# custom_line_V1_mux1.net
KiCad netlist of a schematic drawn in Altium Designer
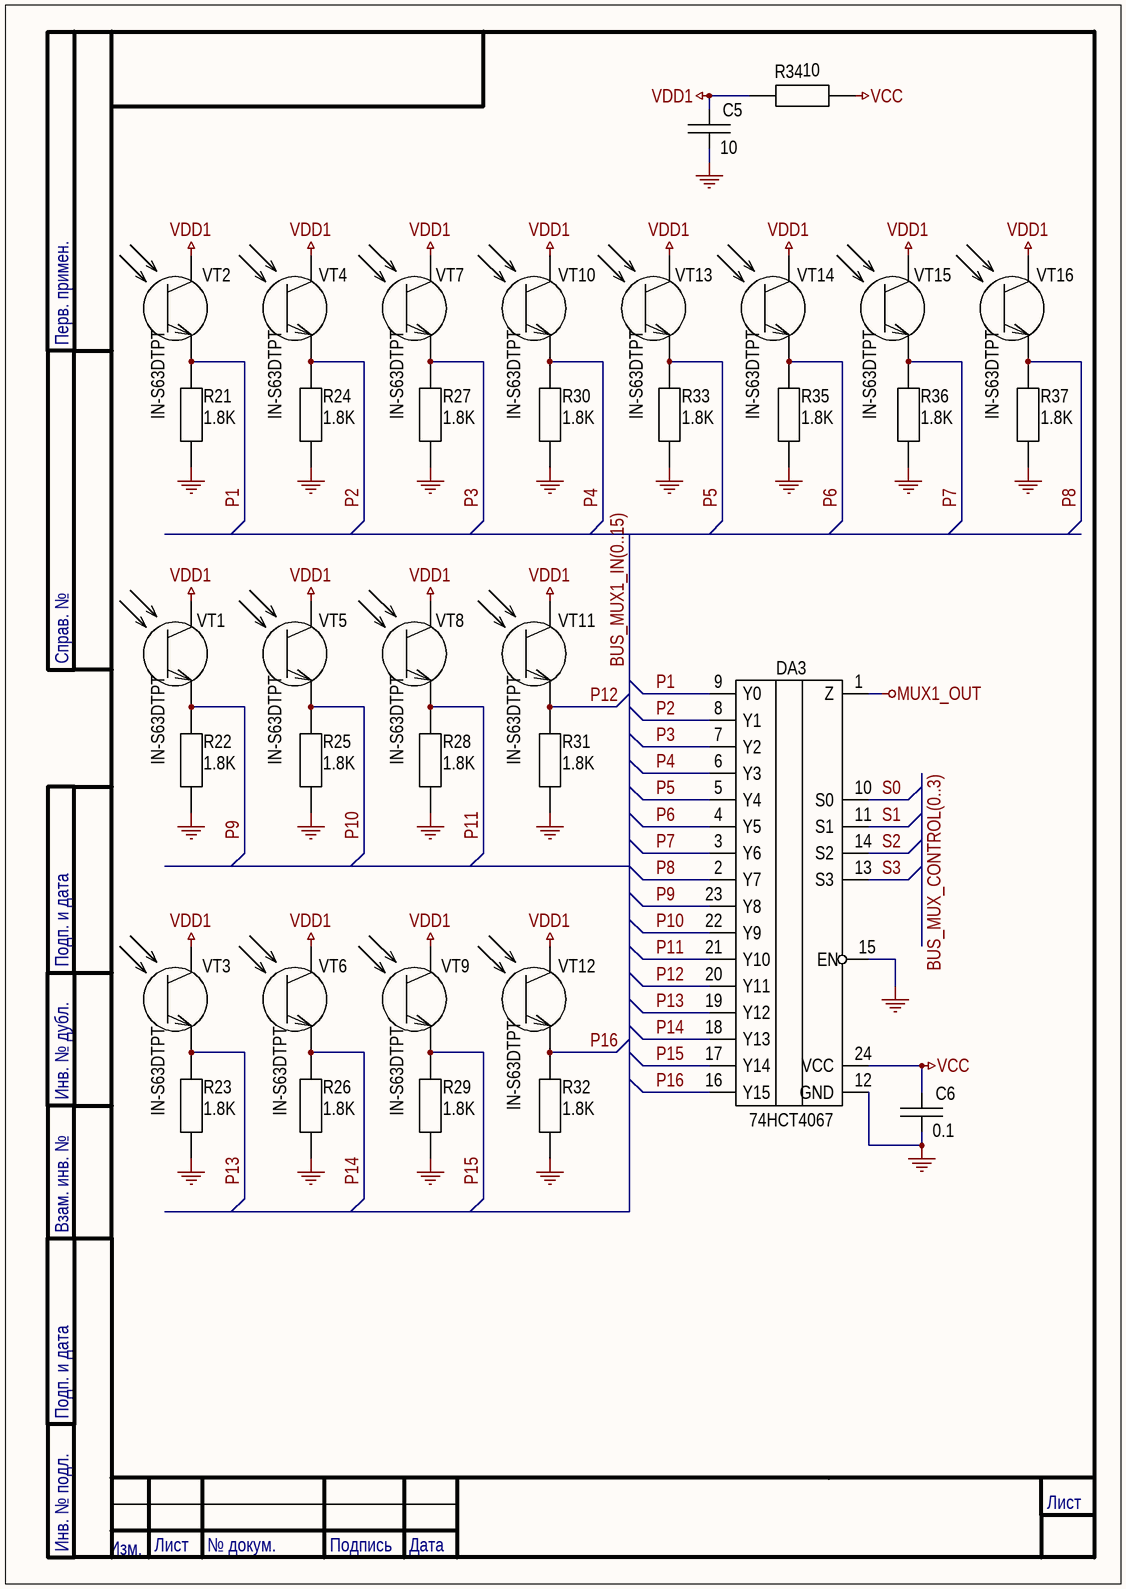
[diagram p0: custom_line_V1_mux1.SchDoc]

(export (version "E")
  (design (tool "Eeschema 10.0.6"))
  (components
    (comp (ref "C5") (value "10") (footprint "CC_0805") (libsource (lib "my_discrete_new") (part "C")))
    (comp (ref "C6") (value "0.1") (footprint "CC_0603") (libsource (lib "my_discrete_new") (part "C")))
    (comp (ref "DA3")
      (value "74HC4067")
      (footprint "TSSOP-24")
      (description "74HC4067PW")
      (fields (field (name "TYPE") "74HCT4067"))
      (libsource (lib "my_microschems_new") (part "74HCT4067"))
    )
    (comp (ref "R21")
      (value "1.8K")
      (footprint "RC_0603_SMALL")
      (fields (field (name "POWER") "0.125W"))
      (libsource (lib "my_discrete_new") (part "R"))
    )
    (comp (ref "R22")
      (value "1.8K")
      (footprint "RC_0603_SMALL")
      (fields (field (name "POWER") "0.125W"))
      (libsource (lib "my_discrete_new") (part "R"))
    )
    (comp (ref "R23")
      (value "1.8K")
      (footprint "RC_0603_SMALL")
      (fields (field (name "POWER") "0.125W"))
      (libsource (lib "my_discrete_new") (part "R"))
    )
    (comp (ref "R24")
      (value "1.8K")
      (footprint "RC_0603_SMALL")
      (fields (field (name "POWER") "0.125W"))
      (libsource (lib "my_discrete_new") (part "R"))
    )
    (comp (ref "R25")
      (value "1.8K")
      (footprint "RC_0603_SMALL")
      (fields (field (name "POWER") "0.125W"))
      (libsource (lib "my_discrete_new") (part "R"))
    )
    (comp (ref "R26")
      (value "1.8K")
      (footprint "RC_0603_SMALL")
      (fields (field (name "POWER") "0.125W"))
      (libsource (lib "my_discrete_new") (part "R"))
    )
    (comp (ref "R27")
      (value "1.8K")
      (footprint "RC_0603_SMALL")
      (fields (field (name "POWER") "0.125W"))
      (libsource (lib "my_discrete_new") (part "R"))
    )
    (comp (ref "R28")
      (value "1.8K")
      (footprint "RC_0603_SMALL")
      (fields (field (name "POWER") "0.125W"))
      (libsource (lib "my_discrete_new") (part "R"))
    )
    (comp (ref "R29")
      (value "1.8K")
      (footprint "RC_0603_SMALL")
      (fields (field (name "POWER") "0.125W"))
      (libsource (lib "my_discrete_new") (part "R"))
    )
    (comp (ref "R30")
      (value "1.8K")
      (footprint "RC_0603_SMALL")
      (fields (field (name "POWER") "0.125W"))
      (libsource (lib "my_discrete_new") (part "R"))
    )
    (comp (ref "R31")
      (value "1.8K")
      (footprint "RC_0603_SMALL")
      (fields (field (name "POWER") "0.125W"))
      (libsource (lib "my_discrete_new") (part "R"))
    )
    (comp (ref "R32")
      (value "1.8K")
      (footprint "RC_0603_SMALL")
      (fields (field (name "POWER") "0.125W"))
      (libsource (lib "my_discrete_new") (part "R"))
    )
    (comp (ref "R33")
      (value "1.8K")
      (footprint "RC_0603_SMALL")
      (fields (field (name "POWER") "0.125W"))
      (libsource (lib "my_discrete_new") (part "R"))
    )
    (comp (ref "R34")
      (value "10")
      (footprint "RC_0603_SMALL")
      (fields (field (name "POWER") "0.125W"))
      (libsource (lib "my_discrete_new") (part "R"))
    )
    (comp (ref "R35")
      (value "1.8K")
      (footprint "RC_0603_SMALL")
      (fields (field (name "POWER") "0.125W"))
      (libsource (lib "my_discrete_new") (part "R"))
    )
    (comp (ref "R36")
      (value "1.8K")
      (footprint "RC_0603_SMALL")
      (fields (field (name "POWER") "0.125W"))
      (libsource (lib "my_discrete_new") (part "R"))
    )
    (comp (ref "R37")
      (value "1.8K")
      (footprint "RC_0603_SMALL")
      (fields (field (name "POWER") "0.125W"))
      (libsource (lib "my_discrete_new") (part "R"))
    )
    (comp (ref "VT1")
      (value "IN-S63DTPT")
      (footprint "LED_0603")
      (description "Phototransistor (Inolux)")
      (libsource (lib "my_discrete_new") (part "phototransistor"))
    )
    (comp (ref "VT2")
      (value "IN-S63DTPT")
      (footprint "LED_0603")
      (description "Phototransistor (Inolux)")
      (libsource (lib "my_discrete_new") (part "phototransistor"))
    )
    (comp (ref "VT3")
      (value "IN-S63DTPT")
      (footprint "LED_0603")
      (description "Phototransistor (Inolux)")
      (libsource (lib "my_discrete_new") (part "phototransistor"))
    )
    (comp (ref "VT4")
      (value "IN-S63DTPT")
      (footprint "LED_0603")
      (description "Phototransistor (Inolux)")
      (libsource (lib "my_discrete_new") (part "phototransistor"))
    )
    (comp (ref "VT5")
      (value "IN-S63DTPT")
      (footprint "LED_0603")
      (description "Phototransistor (Inolux)")
      (libsource (lib "my_discrete_new") (part "phototransistor"))
    )
    (comp (ref "VT6")
      (value "IN-S63DTPT")
      (footprint "LED_0603")
      (description "Phototransistor (Inolux)")
      (libsource (lib "my_discrete_new") (part "phototransistor"))
    )
    (comp (ref "VT7")
      (value "IN-S63DTPT")
      (footprint "LED_0603")
      (description "Phototransistor (Inolux)")
      (libsource (lib "my_discrete_new") (part "phototransistor"))
    )
    (comp (ref "VT8")
      (value "IN-S63DTPT")
      (footprint "LED_0603")
      (description "Phototransistor (Inolux)")
      (libsource (lib "my_discrete_new") (part "phototransistor"))
    )
    (comp (ref "VT9")
      (value "IN-S63DTPT")
      (footprint "LED_0603")
      (description "Phototransistor (Inolux)")
      (libsource (lib "my_discrete_new") (part "phototransistor"))
    )
    (comp (ref "VT10")
      (value "IN-S63DTPT")
      (footprint "LED_0603")
      (description "Phototransistor (Inolux)")
      (libsource (lib "my_discrete_new") (part "phototransistor"))
    )
    (comp (ref "VT11")
      (value "IN-S63DTPT")
      (footprint "LED_0603")
      (description "Phototransistor (Inolux)")
      (libsource (lib "my_discrete_new") (part "phototransistor"))
    )
    (comp (ref "VT12")
      (value "IN-S63DTPT")
      (footprint "LED_0603")
      (description "Phototransistor (Inolux)")
      (libsource (lib "my_discrete_new") (part "phototransistor"))
    )
    (comp (ref "VT13")
      (value "IN-S63DTPT")
      (footprint "LED_0603")
      (description "Phototransistor (Inolux)")
      (libsource (lib "my_discrete_new") (part "phototransistor"))
    )
    (comp (ref "VT14")
      (value "IN-S63DTPT")
      (footprint "LED_0603")
      (description "Phototransistor (Inolux)")
      (libsource (lib "my_discrete_new") (part "phototransistor"))
    )
    (comp (ref "VT15")
      (value "IN-S63DTPT")
      (footprint "LED_0603")
      (description "Phototransistor (Inolux)")
      (libsource (lib "my_discrete_new") (part "phototransistor"))
    )
    (comp (ref "VT16")
      (value "IN-S63DTPT")
      (footprint "LED_0603")
      (description "Phototransistor (Inolux)")
      (libsource (lib "my_discrete_new") (part "phototransistor"))
    )
  )
  (nets
    (net (code "3") (name "/P1") (class "Default")
      (node (ref "DA3") (pin "9") (pinfunction "Y0_9") (pintype "passive"))
      (node (ref "R21") (pin "2") (pinfunction "2_2") (pintype "passive"))
      (node (ref "VT2") (pin "2") (pinfunction "E_2") (pintype "passive"))
    )
    (net (code "4") (name "/P2") (class "Default")
      (node (ref "DA3") (pin "8") (pinfunction "Y1_8") (pintype "passive"))
      (node (ref "R24") (pin "2") (pinfunction "2_2") (pintype "passive"))
      (node (ref "VT4") (pin "2") (pinfunction "E_2") (pintype "passive"))
    )
    (net (code "5") (name "/P3") (class "Default")
      (node (ref "DA3") (pin "7") (pinfunction "Y2_7") (pintype "passive"))
      (node (ref "R27") (pin "2") (pinfunction "2_2") (pintype "passive"))
      (node (ref "VT7") (pin "2") (pinfunction "E_2") (pintype "passive"))
    )
    (net (code "6") (name "/P4") (class "Default")
      (node (ref "DA3") (pin "6") (pinfunction "Y3_6") (pintype "passive"))
      (node (ref "R30") (pin "2") (pinfunction "2_2") (pintype "passive"))
      (node (ref "VT10") (pin "2") (pinfunction "E_2") (pintype "passive"))
    )
    (net (code "7") (name "/P5") (class "Default")
      (node (ref "DA3") (pin "5") (pinfunction "Y4_5") (pintype "passive"))
      (node (ref "R33") (pin "2") (pinfunction "2_2") (pintype "passive"))
      (node (ref "VT13") (pin "2") (pinfunction "E_2") (pintype "passive"))
    )
    (net (code "8") (name "/P6") (class "Default")
      (node (ref "DA3") (pin "4") (pinfunction "Y5_4") (pintype "passive"))
      (node (ref "R35") (pin "2") (pinfunction "2_2") (pintype "passive"))
      (node (ref "VT14") (pin "2") (pinfunction "E_2") (pintype "passive"))
    )
    (net (code "9") (name "/P7") (class "Default")
      (node (ref "DA3") (pin "3") (pinfunction "Y6_3") (pintype "passive"))
      (node (ref "R36") (pin "2") (pinfunction "2_2") (pintype "passive"))
      (node (ref "VT15") (pin "2") (pinfunction "E_2") (pintype "passive"))
    )
    (net (code "10") (name "/P8") (class "Default")
      (node (ref "DA3") (pin "2") (pinfunction "Y7_2") (pintype "passive"))
      (node (ref "R37") (pin "2") (pinfunction "2_2") (pintype "passive"))
      (node (ref "VT16") (pin "2") (pinfunction "E_2") (pintype "passive"))
    )
    (net (code "11") (name "/P9") (class "Default")
      (node (ref "DA3") (pin "23") (pinfunction "Y8_23") (pintype "passive"))
      (node (ref "R22") (pin "2") (pinfunction "2_2") (pintype "passive"))
      (node (ref "VT1") (pin "2") (pinfunction "E_2") (pintype "passive"))
    )
    (net (code "12") (name "/P10") (class "Default")
      (node (ref "DA3") (pin "22") (pinfunction "Y9_22") (pintype "passive"))
      (node (ref "R25") (pin "2") (pinfunction "2_2") (pintype "passive"))
      (node (ref "VT5") (pin "2") (pinfunction "E_2") (pintype "passive"))
    )
    (net (code "13") (name "/P11") (class "Default")
      (node (ref "DA3") (pin "21") (pinfunction "Y10_21") (pintype "passive"))
      (node (ref "R28") (pin "2") (pinfunction "2_2") (pintype "passive"))
      (node (ref "VT8") (pin "2") (pinfunction "E_2") (pintype "passive"))
    )
    (net (code "14") (name "/P12") (class "Default")
      (node (ref "DA3") (pin "20") (pinfunction "Y11_20") (pintype "passive"))
      (node (ref "R31") (pin "2") (pinfunction "2_2") (pintype "passive"))
      (node (ref "VT11") (pin "2") (pinfunction "E_2") (pintype "passive"))
    )
    (net (code "15") (name "/P13") (class "Default")
      (node (ref "DA3") (pin "19") (pinfunction "Y12_19") (pintype "passive"))
      (node (ref "R23") (pin "2") (pinfunction "2_2") (pintype "passive"))
      (node (ref "VT3") (pin "2") (pinfunction "E_2") (pintype "passive"))
    )
    (net (code "16") (name "/P14") (class "Default")
      (node (ref "DA3") (pin "18") (pinfunction "Y13_18") (pintype "passive"))
      (node (ref "R26") (pin "2") (pinfunction "2_2") (pintype "passive"))
      (node (ref "VT6") (pin "2") (pinfunction "E_2") (pintype "passive"))
    )
    (net (code "17") (name "/P15") (class "Default")
      (node (ref "DA3") (pin "17") (pinfunction "Y14_17") (pintype "passive"))
      (node (ref "R29") (pin "2") (pinfunction "2_2") (pintype "passive"))
      (node (ref "VT9") (pin "2") (pinfunction "E_2") (pintype "passive"))
    )
    (net (code "18") (name "/P16") (class "Default")
      (node (ref "DA3") (pin "16") (pinfunction "Y15_16") (pintype "passive"))
      (node (ref "R32") (pin "2") (pinfunction "2_2") (pintype "passive"))
      (node (ref "VT12") (pin "2") (pinfunction "E_2") (pintype "passive"))
    )
    (net (code "19") (name "/S0") (class "Default")
      (node (ref "DA3") (pin "10") (pinfunction "S0_10") (pintype "passive"))
    )
    (net (code "20") (name "/S1") (class "Default")
      (node (ref "DA3") (pin "11") (pinfunction "S1_11") (pintype "passive"))
    )
    (net (code "21") (name "/S2") (class "Default")
      (node (ref "DA3") (pin "14") (pinfunction "S2_14") (pintype "passive"))
    )
    (net (code "22") (name "/S3") (class "Default")
      (node (ref "DA3") (pin "13") (pinfunction "S3_13") (pintype "passive"))
    )
    (net (code "25") (name "GND") (class "Default")
      (node (ref "C5") (pin "1") (pinfunction "1_1") (pintype "passive"))
      (node (ref "C6") (pin "1") (pinfunction "1_1") (pintype "passive"))
      (node (ref "DA3") (pin "12") (pinfunction "GND_12") (pintype "power_in"))
      (node (ref "DA3") (pin "15") (pinfunction "EN_15") (pintype "passive"))
      (node (ref "R21") (pin "1") (pinfunction "1_1") (pintype "passive"))
      (node (ref "R22") (pin "1") (pinfunction "1_1") (pintype "passive"))
      (node (ref "R23") (pin "1") (pinfunction "1_1") (pintype "passive"))
      (node (ref "R24") (pin "1") (pinfunction "1_1") (pintype "passive"))
      (node (ref "R25") (pin "1") (pinfunction "1_1") (pintype "passive"))
      (node (ref "R26") (pin "1") (pinfunction "1_1") (pintype "passive"))
      (node (ref "R27") (pin "1") (pinfunction "1_1") (pintype "passive"))
      (node (ref "R28") (pin "1") (pinfunction "1_1") (pintype "passive"))
      (node (ref "R29") (pin "1") (pinfunction "1_1") (pintype "passive"))
      (node (ref "R30") (pin "1") (pinfunction "1_1") (pintype "passive"))
      (node (ref "R31") (pin "1") (pinfunction "1_1") (pintype "passive"))
      (node (ref "R32") (pin "1") (pinfunction "1_1") (pintype "passive"))
      (node (ref "R33") (pin "1") (pinfunction "1_1") (pintype "passive"))
      (node (ref "R35") (pin "1") (pinfunction "1_1") (pintype "passive"))
      (node (ref "R36") (pin "1") (pinfunction "1_1") (pintype "passive"))
      (node (ref "R37") (pin "1") (pinfunction "1_1") (pintype "passive"))
    )
    (net (code "26") (name "MUX1_OUT") (class "Default")
      (node (ref "DA3") (pin "1") (pinfunction "Z_1") (pintype "passive"))
    )
    (net (code "27") (name "VCC") (class "Default")
      (node (ref "C6") (pin "2") (pinfunction "2_2") (pintype "passive"))
      (node (ref "DA3") (pin "24") (pinfunction "VCC_24") (pintype "power_in"))
      (node (ref "R34") (pin "1") (pinfunction "1_1") (pintype "passive"))
    )
    (net (code "28") (name "VDD1") (class "Default")
      (node (ref "C5") (pin "2") (pinfunction "2_2") (pintype "passive"))
      (node (ref "R34") (pin "2") (pinfunction "2_2") (pintype "passive"))
      (node (ref "VT1") (pin "1") (pinfunction "C_1") (pintype "passive"))
      (node (ref "VT10") (pin "1") (pinfunction "C_1") (pintype "passive"))
      (node (ref "VT11") (pin "1") (pinfunction "C_1") (pintype "passive"))
      (node (ref "VT12") (pin "1") (pinfunction "C_1") (pintype "passive"))
      (node (ref "VT13") (pin "1") (pinfunction "C_1") (pintype "passive"))
      (node (ref "VT14") (pin "1") (pinfunction "C_1") (pintype "passive"))
      (node (ref "VT15") (pin "1") (pinfunction "C_1") (pintype "passive"))
      (node (ref "VT16") (pin "1") (pinfunction "C_1") (pintype "passive"))
      (node (ref "VT2") (pin "1") (pinfunction "C_1") (pintype "passive"))
      (node (ref "VT3") (pin "1") (pinfunction "C_1") (pintype "passive"))
      (node (ref "VT4") (pin "1") (pinfunction "C_1") (pintype "passive"))
      (node (ref "VT5") (pin "1") (pinfunction "C_1") (pintype "passive"))
      (node (ref "VT6") (pin "1") (pinfunction "C_1") (pintype "passive"))
      (node (ref "VT7") (pin "1") (pinfunction "C_1") (pintype "passive"))
      (node (ref "VT8") (pin "1") (pinfunction "C_1") (pintype "passive"))
      (node (ref "VT9") (pin "1") (pinfunction "C_1") (pintype "passive"))
    )
  )
)
